# EnvironmentMonitorV4_1.net
KiCad netlist of a schematic drawn in EAGLE
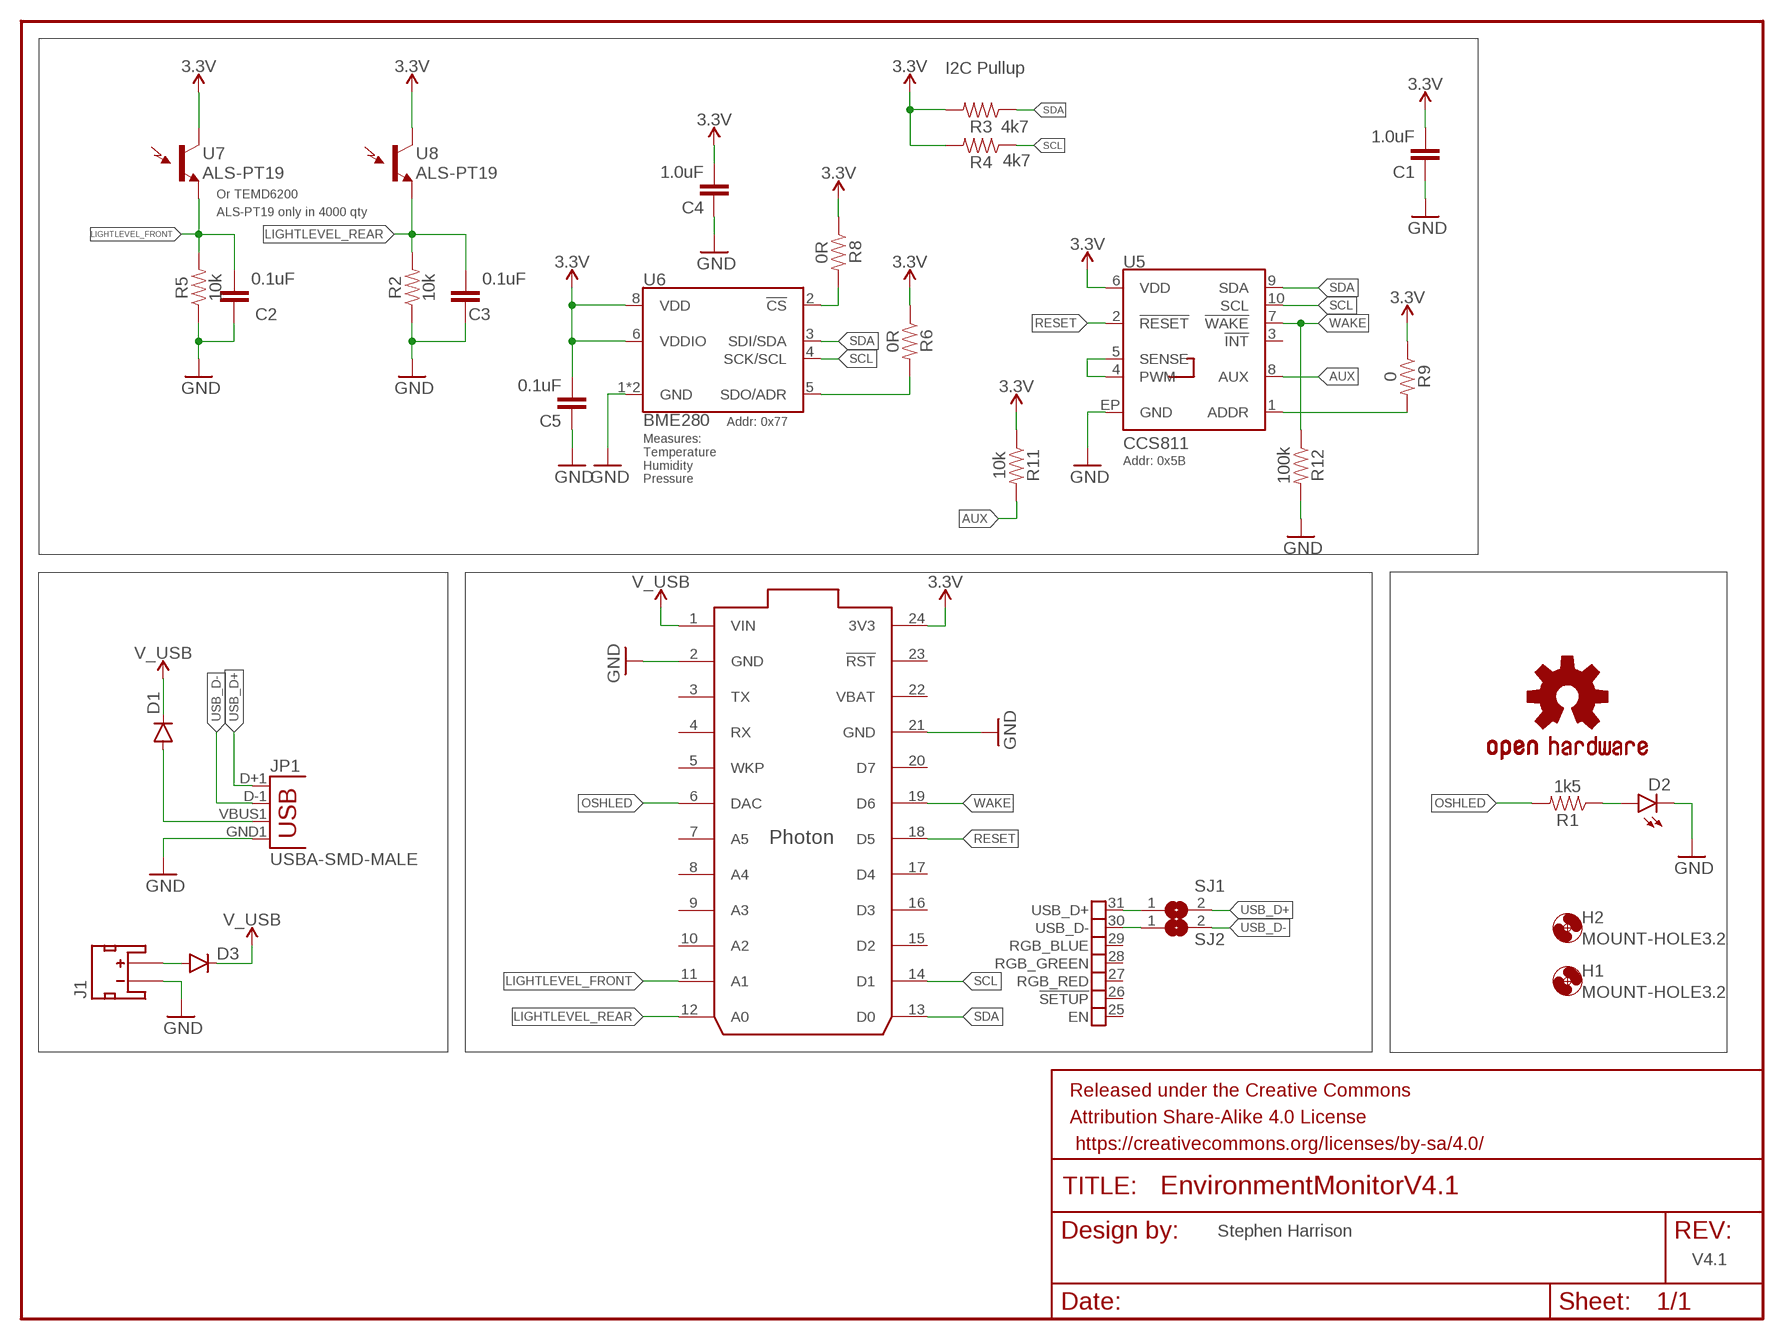
[diagram p0: schematic, sheet 1]

(export (version "E")
  (design (tool "Eeschema 10.0.6"))
  (components
    (comp (ref "C1")
      (value "1.0uF")
      (footprint "eagle-import:0805-CAP")
      (libsource (lib "eagle-import") (part "1.0UF-25V-+80/-20(0805){dblquote}"))
    )
    (comp (ref "C2")
      (value "0.1uF")
      (footprint "eagle-import:0805-CAP")
      (libsource (lib "eagle-import") (part "1.0UF-25V-+80/-20(0805){dblquote}"))
    )
    (comp (ref "C3")
      (value "0.1uF")
      (footprint "eagle-import:0805-CAP")
      (libsource (lib "eagle-import") (part "1.0UF-25V-+80/-20(0805){dblquote}"))
    )
    (comp (ref "C4")
      (value "1.0uF")
      (footprint "eagle-import:0805-CAP")
      (libsource (lib "eagle-import") (part "1.0UF-25V-+80/-20(0805){dblquote}"))
    )
    (comp (ref "C5")
      (value "0.1uF")
      (footprint "eagle-import:0805-CAP")
      (libsource (lib "eagle-import") (part "1.0UF-25V-+80/-20(0805){dblquote}"))
    )
    (comp (ref "D1")
      (value "DIODESMA")
      (footprint "eagle-import:SMA-DIODE")
      (libsource (lib "eagle-import") (part "DIODESMA"))
    )
    (comp (ref "D2")
      (value "LED1206-BOTTOM")
      (footprint "eagle-import:LED-1206-BOTTOM")
      (libsource (lib "eagle-import") (part "LED1206-BOTTOM"))
    )
    (comp (ref "D3")
      (value "DIODESMA")
      (footprint "eagle-import:SMA-DIODE")
      (libsource (lib "eagle-import") (part "DIODESMA"))
    )
    (comp (ref "FRAME1")
      (value "FRAME-LETTER")
      (footprint "eagle-import:CREATIVE_COMMONS")
      (libsource (lib "eagle-import") (part "FRAME-LETTER"))
    )
    (comp (ref "H1")
      (value "MOUNT-HOLE3.2")
      (footprint "eagle-import:3,2")
      (libsource (lib "eagle-import") (part "MOUNT-HOLE3.2"))
    )
    (comp (ref "H2")
      (value "MOUNT-HOLE3.2")
      (footprint "eagle-import:3,2")
      (libsource (lib "eagle-import") (part "MOUNT-HOLE3.2"))
    )
    (comp (ref "J1")
      (value "JST_2MM_MALE")
      (footprint "eagle-import:JST-2-SMD")
      (libsource (lib "eagle-import") (part "JST_2MM_MALE"))
    )
    (comp (ref "JP1")
      (value "USBA-SMD-MALE")
      (footprint "eagle-import:USB-A-SMT-MALE")
      (libsource (lib "eagle-import") (part "USBA-SMD-MALE"))
    )
    (comp (ref "LOGO1")
      (value "OSHW-LOGOM")
      (footprint "eagle-import:OSHW-LOGO-M")
      (libsource (lib "eagle-import") (part "OSHW-LOGOM"))
    )
    (comp (ref "R1")
      (value "1k5")
      (footprint "eagle-import:0805")
      (libsource (lib "eagle-import") (part "RESISTOR0805"))
    )
    (comp (ref "R2")
      (value "10k")
      (footprint "eagle-import:0805")
      (libsource (lib "eagle-import") (part "RESISTOR0805"))
    )
    (comp (ref "R3")
      (value "4k7")
      (footprint "eagle-import:0805")
      (libsource (lib "eagle-import") (part "RESISTOR0805"))
    )
    (comp (ref "R4")
      (value "4k7")
      (footprint "eagle-import:0805")
      (libsource (lib "eagle-import") (part "RESISTOR0805"))
    )
    (comp (ref "R5")
      (value "10k")
      (footprint "eagle-import:0805")
      (libsource (lib "eagle-import") (part "RESISTOR0805"))
    )
    (comp (ref "R6")
      (value "0R")
      (footprint "eagle-import:0805")
      (libsource (lib "eagle-import") (part "RESISTOR0805"))
    )
    (comp (ref "R8")
      (value "0R")
      (footprint "eagle-import:0805")
      (libsource (lib "eagle-import") (part "RESISTOR0805"))
    )
    (comp (ref "R9")
      (value "0")
      (footprint "eagle-import:0805")
      (libsource (lib "eagle-import") (part "RESISTOR0805"))
    )
    (comp (ref "R11")
      (value "10k")
      (footprint "eagle-import:0805")
      (libsource (lib "eagle-import") (part "RESISTOR0805"))
    )
    (comp (ref "R12")
      (value "100k")
      (footprint "eagle-import:0805")
      (libsource (lib "eagle-import") (part "RESISTOR0805"))
    )
    (comp (ref "SJ1") (value "SJ") (footprint "eagle-import:SJ") (libsource (lib "eagle-import") (part "SJ")))
    (comp (ref "SJ2") (value "SJ") (footprint "eagle-import:SJ") (libsource (lib "eagle-import") (part "SJ")))
    (comp (ref "U$1")
      (value "PHOTON_SMD")
      (footprint "eagle-import:PHOTON_SMD")
      (libsource (lib "eagle-import") (part "PHOTON_SMD"))
    )
    (comp (ref "U5")
      (value "CCS811")
      (footprint "eagle-import:LGA10")
      (libsource (lib "eagle-import") (part "CCS811"))
    )
    (comp (ref "U6")
      (value "BME280")
      (footprint "eagle-import:LGA-8-2.5X2.5")
      (libsource (lib "eagle-import") (part "BME280"))
    )
    (comp (ref "U7")
      (value "ALS-PT19")
      (footprint "eagle-import:ALS-PT19")
      (libsource (lib "eagle-import") (part "LIGHT_SENSORALS"))
    )
    (comp (ref "U8")
      (value "ALS-PT19")
      (footprint "eagle-import:ALS-PT19")
      (libsource (lib "eagle-import") (part "LIGHT_SENSORALS"))
    )
  )
  (nets
    (net (code "1") (name "/VBAT") (class "Default")
      (node (ref "U$1") (pin "22") (pinfunction "VBAT_22") (pintype "power_in"))
    )
    (net (code "2") (name "3.3V") (class "Default")
      (node (ref "C1") (pin "2") (pinfunction "2_2") (pintype "passive"))
      (node (ref "C4") (pin "2") (pinfunction "2_2") (pintype "passive"))
      (node (ref "C5") (pin "2") (pinfunction "2_2") (pintype "passive"))
      (node (ref "R11") (pin "1") (pinfunction "1_1") (pintype "passive"))
      (node (ref "R3") (pin "2") (pinfunction "2_2") (pintype "passive"))
      (node (ref "R4") (pin "2") (pinfunction "2_2") (pintype "passive"))
      (node (ref "R6") (pin "1") (pinfunction "1_1") (pintype "passive"))
      (node (ref "R8") (pin "1") (pinfunction "1_1") (pintype "passive"))
      (node (ref "R9") (pin "1") (pinfunction "1_1") (pintype "passive"))
      (node (ref "U$1") (pin "24") (pinfunction "3V3_24") (pintype "power_in"))
      (node (ref "U5") (pin "6") (pinfunction "VDD_6") (pintype "bidirectional"))
      (node (ref "U6") (pin "6") (pinfunction "VDDIO_6") (pintype "bidirectional"))
      (node (ref "U6") (pin "8") (pinfunction "VDD_8") (pintype "bidirectional"))
      (node (ref "U7") (pin "C") (pinfunction "C1_C") (pintype "passive"))
      (node (ref "U8") (pin "C") (pinfunction "C1_C") (pintype "passive"))
    )
    (net (code "3") (name "AUX") (class "Default")
      (node (ref "R11") (pin "2") (pinfunction "2_2") (pintype "passive"))
      (node (ref "U5") (pin "8") (pinfunction "AUX_8") (pintype "bidirectional"))
    )
    (net (code "4") (name "GND") (class "Default")
      (node (ref "C1") (pin "1") (pinfunction "1_1") (pintype "passive"))
      (node (ref "C2") (pin "1") (pinfunction "1_1") (pintype "passive"))
      (node (ref "C3") (pin "1") (pinfunction "1_1") (pintype "passive"))
      (node (ref "C4") (pin "1") (pinfunction "1_1") (pintype "passive"))
      (node (ref "C5") (pin "1") (pinfunction "1_1") (pintype "passive"))
      (node (ref "D2") (pin "C") (pinfunction "C_C") (pintype "passive"))
      (node (ref "J1") (pin "1") (pinfunction "-_1") (pintype "bidirectional"))
      (node (ref "JP1") (pin "GND1") (pinfunction "GND_GND1") (pintype "bidirectional"))
      (node (ref "R12") (pin "2") (pinfunction "2_2") (pintype "passive"))
      (node (ref "R2") (pin "1") (pinfunction "1_1") (pintype "passive"))
      (node (ref "R5") (pin "1") (pinfunction "1_1") (pintype "passive"))
      (node (ref "U$1") (pin "2") (pinfunction "GND_2") (pintype "power_in"))
      (node (ref "U$1") (pin "21") (pinfunction "GND_21") (pintype "power_in"))
      (node (ref "U5") (pin "EP") (pinfunction "GND_EP") (pintype "bidirectional"))
      (node (ref "U6") (pin "1") (pinfunction "GND_1") (pintype "bidirectional"))
      (node (ref "U6") (pin "7") (pinfunction "GND_7") (pintype "bidirectional"))
    )
    (net (code "5") (name "LIGHTLEVEL_FRONT") (class "Default")
      (node (ref "C2") (pin "2") (pinfunction "2_2") (pintype "passive"))
      (node (ref "R5") (pin "2") (pinfunction "2_2") (pintype "passive"))
      (node (ref "U$1") (pin "11") (pinfunction "A1_11") (pintype "bidirectional"))
      (node (ref "U7") (pin "E") (pinfunction "E1_E") (pintype "passive"))
    )
    (net (code "6") (name "LIGHTLEVEL_REAR") (class "Default")
      (node (ref "C3") (pin "2") (pinfunction "2_2") (pintype "passive"))
      (node (ref "R2") (pin "2") (pinfunction "2_2") (pintype "passive"))
      (node (ref "U$1") (pin "12") (pinfunction "A0_12") (pintype "bidirectional"))
      (node (ref "U8") (pin "E") (pinfunction "E1_E") (pintype "passive"))
    )
    (net (code "7") (name "Net-(D2-PadA)") (class "Default")
      (node (ref "D2") (pin "A") (pinfunction "A_A") (pintype "passive"))
      (node (ref "R1") (pin "1") (pinfunction "1_1") (pintype "passive"))
    )
    (net (code "8") (name "Net-(J1-+)") (class "Default")
      (node (ref "D3") (pin "A") (pinfunction "A_A") (pintype "passive"))
      (node (ref "J1") (pin "2") (pinfunction "+_2") (pintype "bidirectional"))
    )
    (net (code "9") (name "Net-(JP1-VBUS)") (class "Default")
      (node (ref "D1") (pin "A") (pinfunction "A_A") (pintype "passive"))
      (node (ref "JP1") (pin "VBUS1") (pinfunction "VBUS_VBUS1") (pintype "bidirectional"))
    )
    (net (code "10") (name "Net-(U$1B-USB_D+)") (class "Default")
      (node (ref "SJ1") (pin "1") (pinfunction "1_1") (pintype "passive"))
      (node (ref "U$1") (pin "31") (pinfunction "USB_D+_31") (pintype "bidirectional"))
    )
    (net (code "11") (name "Net-(U$1B-USB_D-)") (class "Default")
      (node (ref "SJ2") (pin "1") (pinfunction "1_1") (pintype "passive"))
      (node (ref "U$1") (pin "30") (pinfunction "USB_D-_30") (pintype "bidirectional"))
    )
    (net (code "12") (name "Net-(U5-ADDR)") (class "Default")
      (node (ref "R9") (pin "2") (pinfunction "2_2") (pintype "passive"))
      (node (ref "U5") (pin "1") (pinfunction "ADDR_1") (pintype "bidirectional"))
    )
    (net (code "13") (name "Net-(U5-PWM)") (class "Default")
      (node (ref "U5") (pin "4") (pinfunction "PWM_4") (pintype "bidirectional"))
      (node (ref "U5") (pin "5") (pinfunction "SENSE_5") (pintype "bidirectional"))
    )
    (net (code "14") (name "Net-(U6-SDO{slash}ADR)") (class "Default")
      (node (ref "R6") (pin "2") (pinfunction "2_2") (pintype "passive"))
      (node (ref "U6") (pin "5") (pinfunction "SDO/ADR_5") (pintype "bidirectional"))
    )
    (net (code "15") (name "Net-(U6-~{CS})") (class "Default")
      (node (ref "R8") (pin "2") (pinfunction "2_2") (pintype "passive"))
      (node (ref "U6") (pin "2") (pinfunction "~{CS}_2") (pintype "bidirectional"))
    )
    (net (code "16") (name "OSHLED") (class "Default")
      (node (ref "R1") (pin "2") (pinfunction "2_2") (pintype "passive"))
      (node (ref "U$1") (pin "6") (pinfunction "DAC_6") (pintype "bidirectional"))
    )
    (net (code "17") (name "RESET") (class "Default")
      (node (ref "U$1") (pin "18") (pinfunction "D5_18") (pintype "bidirectional"))
      (node (ref "U5") (pin "2") (pinfunction "~{RESET}_2") (pintype "bidirectional"))
    )
    (net (code "18") (name "SCL") (class "Default")
      (node (ref "R4") (pin "1") (pinfunction "1_1") (pintype "passive"))
      (node (ref "U$1") (pin "14") (pinfunction "D1_14") (pintype "bidirectional"))
      (node (ref "U5") (pin "10") (pinfunction "SCL_10") (pintype "bidirectional"))
      (node (ref "U6") (pin "4") (pinfunction "SCK/SCL_4") (pintype "bidirectional"))
    )
    (net (code "19") (name "SDA") (class "Default")
      (node (ref "R3") (pin "1") (pinfunction "1_1") (pintype "passive"))
      (node (ref "U$1") (pin "13") (pinfunction "D0_13") (pintype "bidirectional"))
      (node (ref "U5") (pin "9") (pinfunction "SDA_9") (pintype "bidirectional"))
      (node (ref "U6") (pin "3") (pinfunction "SDI/SDA_3") (pintype "bidirectional"))
    )
    (net (code "20") (name "USB_D+") (class "Default")
      (node (ref "JP1") (pin "D+1") (pinfunction "D+_D+1") (pintype "bidirectional"))
      (node (ref "SJ1") (pin "2") (pinfunction "2_2") (pintype "passive"))
    )
    (net (code "21") (name "USB_D-") (class "Default")
      (node (ref "JP1") (pin "D-1") (pinfunction "D-_D-1") (pintype "bidirectional"))
      (node (ref "SJ2") (pin "2") (pinfunction "2_2") (pintype "passive"))
    )
    (net (code "22") (name "V_USB") (class "Default")
      (node (ref "D1") (pin "C") (pinfunction "C_C") (pintype "passive"))
      (node (ref "D3") (pin "C") (pinfunction "C_C") (pintype "passive"))
      (node (ref "U$1") (pin "1") (pinfunction "VIN_1") (pintype "power_in"))
    )
    (net (code "23") (name "WAKE") (class "Default")
      (node (ref "R12") (pin "1") (pinfunction "1_1") (pintype "passive"))
      (node (ref "U$1") (pin "19") (pinfunction "D6_19") (pintype "bidirectional"))
      (node (ref "U5") (pin "7") (pinfunction "~{WAKE}_7") (pintype "bidirectional"))
    )
    (net (code "24") (name "unconnected-(J1-PAD1-PadNC1)") (class "Default")
      (node (ref "J1") (pin "NC1") (pinfunction "PAD1_NC1") (pintype "bidirectional"))
    )
    (net (code "25") (name "unconnected-(J1-PAD2-PadNC2)") (class "Default")
      (node (ref "J1") (pin "NC2") (pinfunction "PAD2_NC2") (pintype "bidirectional"))
    )
    (net (code "26") (name "unconnected-(U$1A-A2-Pad10)") (class "Default")
      (node (ref "U$1") (pin "10") (pinfunction "A2_10") (pintype "bidirectional"))
    )
    (net (code "27") (name "unconnected-(U$1A-A3-Pad9)") (class "Default")
      (node (ref "U$1") (pin "9") (pinfunction "A3_9") (pintype "bidirectional"))
    )
    (net (code "28") (name "unconnected-(U$1A-A4-Pad8)") (class "Default")
      (node (ref "U$1") (pin "8") (pinfunction "A4_8") (pintype "bidirectional"))
    )
    (net (code "29") (name "unconnected-(U$1A-A5-Pad7)") (class "Default")
      (node (ref "U$1") (pin "7") (pinfunction "A5_7") (pintype "bidirectional"))
    )
    (net (code "30") (name "unconnected-(U$1A-D2-Pad15)") (class "Default")
      (node (ref "U$1") (pin "15") (pinfunction "D2_15") (pintype "bidirectional"))
    )
    (net (code "31") (name "unconnected-(U$1A-D3-Pad16)") (class "Default")
      (node (ref "U$1") (pin "16") (pinfunction "D3_16") (pintype "bidirectional"))
    )
    (net (code "32") (name "unconnected-(U$1A-D4-Pad17)") (class "Default")
      (node (ref "U$1") (pin "17") (pinfunction "D4_17") (pintype "bidirectional"))
    )
    (net (code "33") (name "unconnected-(U$1A-D7-Pad20)") (class "Default")
      (node (ref "U$1") (pin "20") (pinfunction "D7_20") (pintype "bidirectional"))
    )
    (net (code "34") (name "unconnected-(U$1A-RX-Pad4)") (class "Default")
      (node (ref "U$1") (pin "4") (pinfunction "RX_4") (pintype "bidirectional"))
    )
    (net (code "35") (name "unconnected-(U$1A-TX-Pad3)") (class "Default")
      (node (ref "U$1") (pin "3") (pinfunction "TX_3") (pintype "bidirectional"))
    )
    (net (code "36") (name "unconnected-(U$1A-WKP-Pad5)") (class "Default")
      (node (ref "U$1") (pin "5") (pinfunction "WKP_5") (pintype "bidirectional"))
    )
    (net (code "37") (name "unconnected-(U$1A-~{RST}-Pad23)") (class "Default")
      (node (ref "U$1") (pin "23") (pinfunction "~{RST}_23") (pintype "bidirectional"))
    )
    (net (code "38") (name "unconnected-(U$1B-EN-Pad25)") (class "Default")
      (node (ref "U$1") (pin "25") (pinfunction "EN_25") (pintype "bidirectional"))
    )
    (net (code "39") (name "unconnected-(U$1B-RGB_BLUE-Pad29)") (class "Default")
      (node (ref "U$1") (pin "29") (pinfunction "RGB_BLUE_29") (pintype "bidirectional"))
    )
    (net (code "40") (name "unconnected-(U$1B-RGB_GREEN-Pad28)") (class "Default")
      (node (ref "U$1") (pin "28") (pinfunction "RGB_GREEN_28") (pintype "bidirectional"))
    )
    (net (code "41") (name "unconnected-(U$1B-RGB_RED-Pad27)") (class "Default")
      (node (ref "U$1") (pin "27") (pinfunction "RGB_RED_27") (pintype "bidirectional"))
    )
    (net (code "42") (name "unconnected-(U$1B-~{SETUP}-Pad26)") (class "Default")
      (node (ref "U$1") (pin "26") (pinfunction "~{SETUP}_26") (pintype "bidirectional"))
    )
    (net (code "43") (name "unconnected-(U5-~{INT}-Pad3)") (class "Default")
      (node (ref "U5") (pin "3") (pinfunction "~{INT}_3") (pintype "bidirectional"))
    )
  )
)
